# Sheet4.net
KiCad netlist of a schematic drawn in Altium Designer
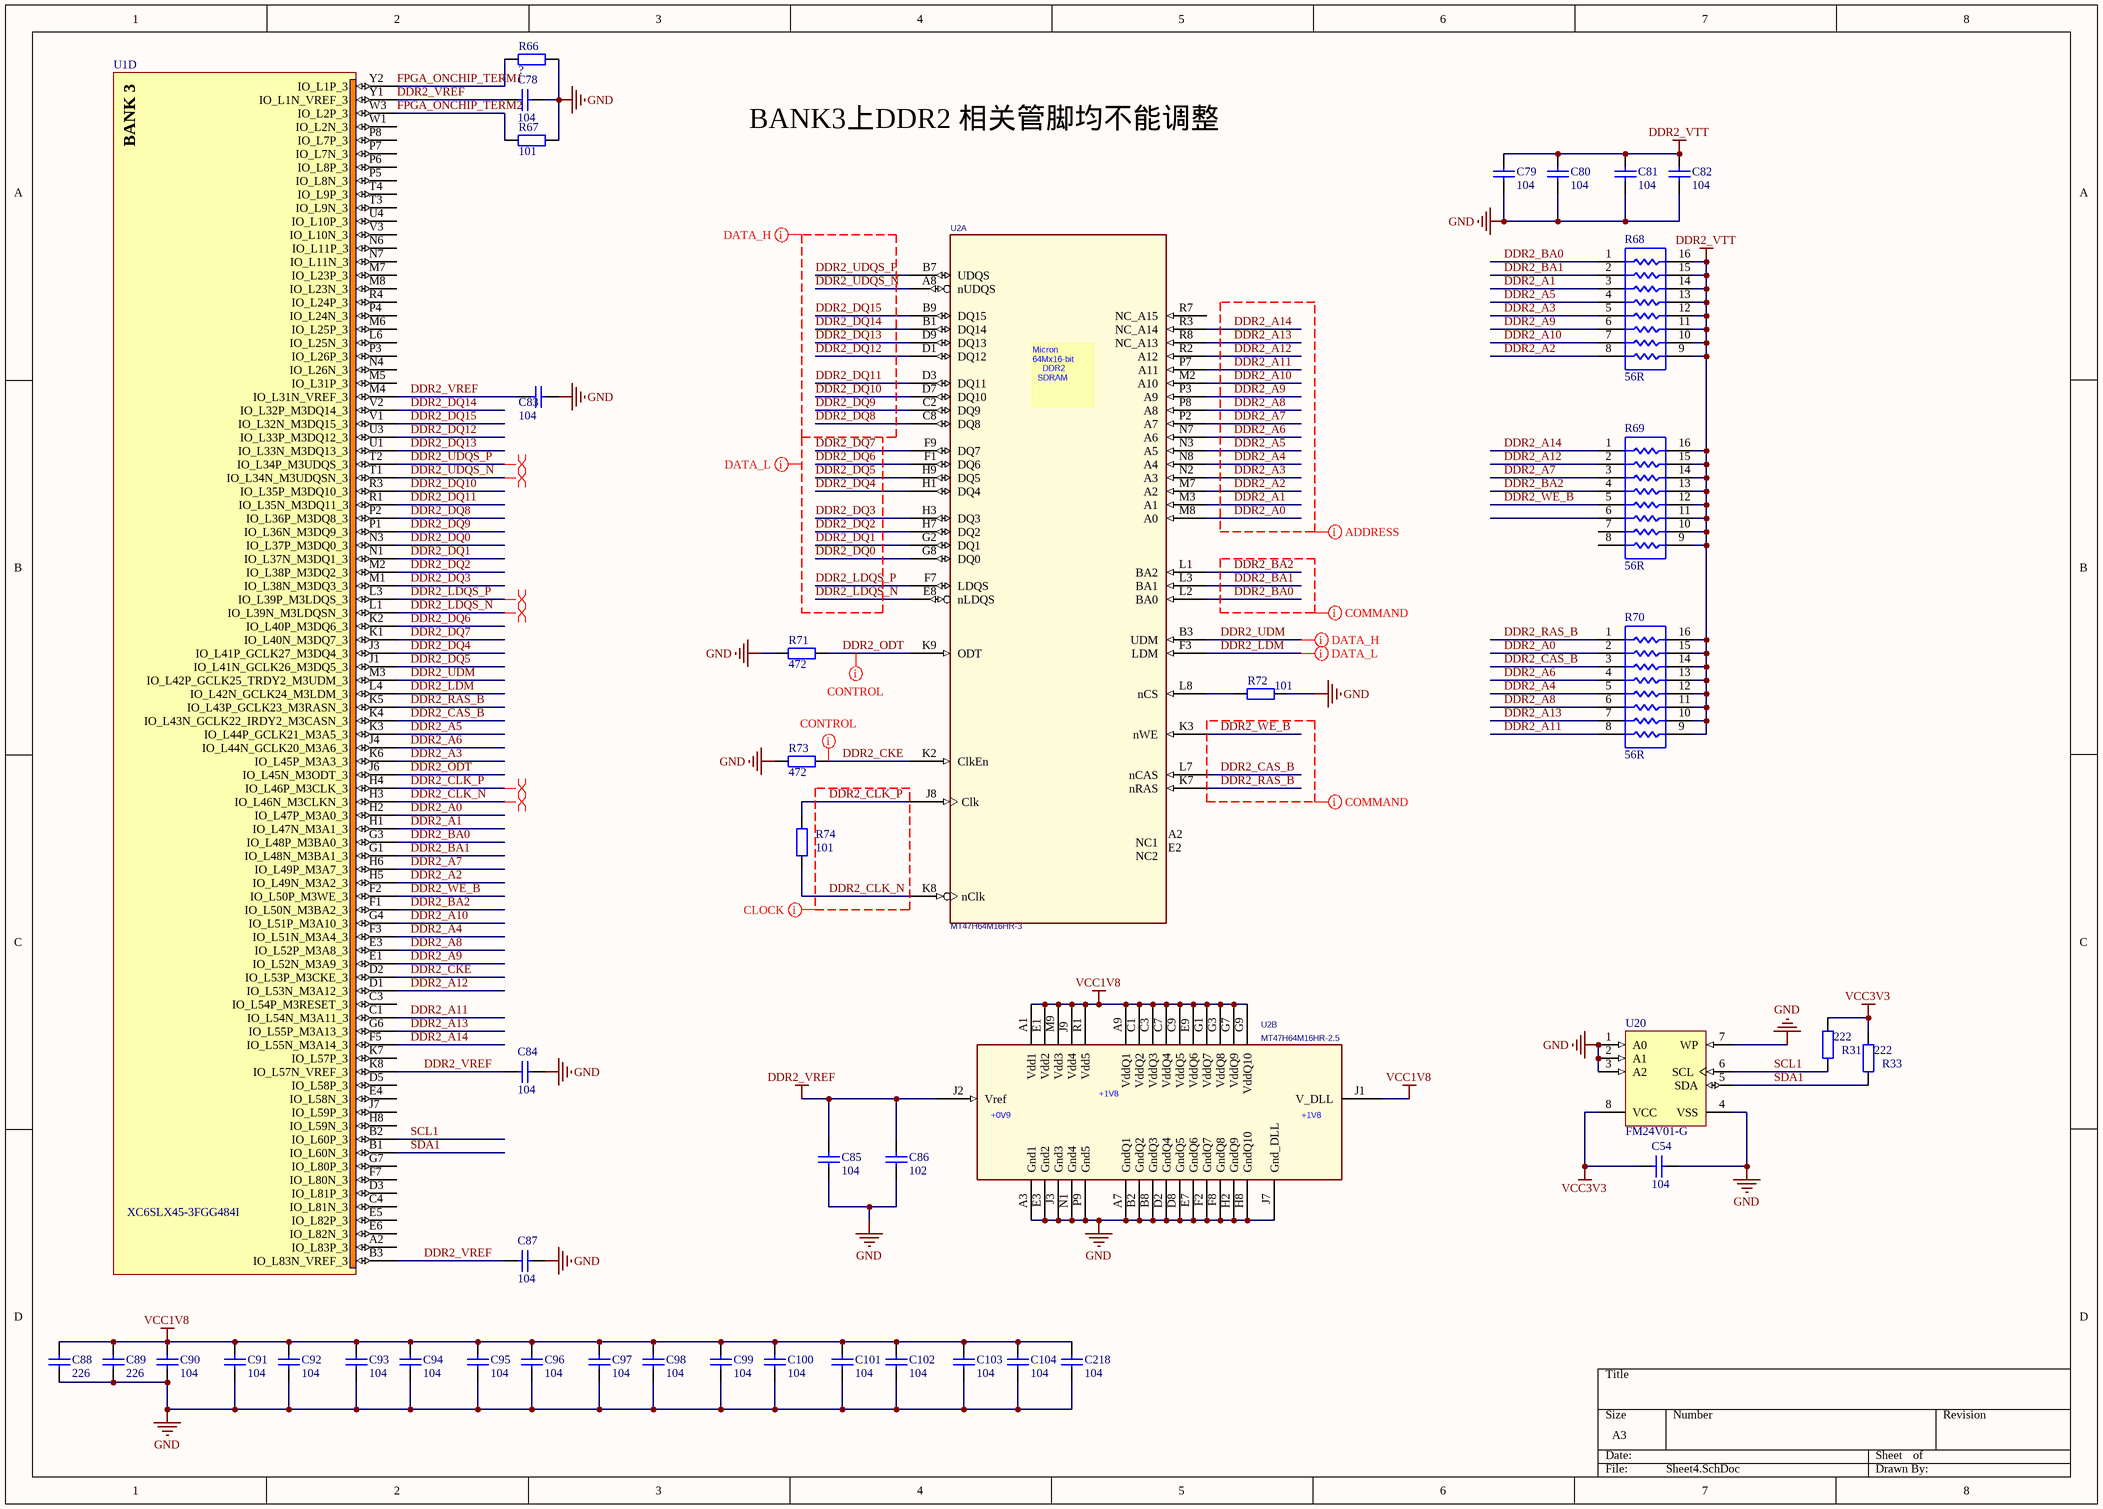
[diagram p0: Sheet4.SchDoc]

(export (version "E")
  (design (tool "Eeschema 10.0.6"))
  (components
    (comp (ref "C54")
      (value "104")
      (footprint "0402")
      (description "Capacitor")
      (fields (field (name "PUBLISHER") "Altium Limited"))
      (libsource (lib "Miscellaneous Devices") (part "Cap"))
    )
    (comp (ref "C78")
      (value "104")
      (footprint "0402")
      (description "Capacitor")
      (fields (field (name "PUBLISHER") "Altium Limited"))
      (libsource (lib "Miscellaneous Devices") (part "Cap"))
    )
    (comp (ref "C79")
      (value "104")
      (footprint "0402")
      (description "Capacitor")
      (fields (field (name "PUBLISHER") "Altium Limited"))
      (libsource (lib "Miscellaneous Devices") (part "Cap"))
    )
    (comp (ref "C80")
      (value "104")
      (footprint "0402")
      (description "Capacitor")
      (fields (field (name "PUBLISHER") "Altium Limited"))
      (libsource (lib "Miscellaneous Devices") (part "Cap"))
    )
    (comp (ref "C81")
      (value "104")
      (footprint "0402")
      (description "Capacitor")
      (fields (field (name "PUBLISHER") "Altium Limited"))
      (libsource (lib "Miscellaneous Devices") (part "Cap"))
    )
    (comp (ref "C82")
      (value "104")
      (footprint "0402")
      (description "Capacitor")
      (fields (field (name "PUBLISHER") "Altium Limited"))
      (libsource (lib "Miscellaneous Devices") (part "Cap"))
    )
    (comp (ref "C83")
      (value "104")
      (footprint "0402")
      (description "Capacitor")
      (fields (field (name "PUBLISHER") "Altium Limited"))
      (libsource (lib "Miscellaneous Devices") (part "Cap"))
    )
    (comp (ref "C84")
      (value "104")
      (footprint "0402")
      (description "Capacitor")
      (fields (field (name "PUBLISHER") "Altium Limited"))
      (libsource (lib "Miscellaneous Devices") (part "Cap"))
    )
    (comp (ref "C85")
      (value "104")
      (footprint "0402")
      (description "Capacitor")
      (fields (field (name "PUBLISHER") "Altium Limited"))
      (libsource (lib "Miscellaneous Devices") (part "Cap"))
    )
    (comp (ref "C86")
      (value "102")
      (footprint "0402")
      (description "Capacitor")
      (fields (field (name "PUBLISHER") "Altium Limited"))
      (libsource (lib "Miscellaneous Devices") (part "Cap"))
    )
    (comp (ref "C87")
      (value "104")
      (footprint "0402")
      (description "Capacitor")
      (fields (field (name "PUBLISHER") "Altium Limited"))
      (libsource (lib "Miscellaneous Devices") (part "Cap"))
    )
    (comp (ref "C88")
      (value "226")
      (footprint "0603")
      (description "Capacitor")
      (fields (field (name "PUBLISHER") "Altium Limited"))
      (libsource (lib "Miscellaneous Devices") (part "Cap"))
    )
    (comp (ref "C89")
      (value "226")
      (footprint "0603")
      (description "Capacitor")
      (fields (field (name "PUBLISHER") "Altium Limited"))
      (libsource (lib "Miscellaneous Devices") (part "Cap"))
    )
    (comp (ref "C90")
      (value "104")
      (footprint "0402")
      (description "Capacitor")
      (fields (field (name "PUBLISHER") "Altium Limited"))
      (libsource (lib "Miscellaneous Devices") (part "Cap"))
    )
    (comp (ref "C91")
      (value "104")
      (footprint "0402")
      (description "Capacitor")
      (fields (field (name "PUBLISHER") "Altium Limited"))
      (libsource (lib "Miscellaneous Devices") (part "Cap"))
    )
    (comp (ref "C92")
      (value "104")
      (footprint "0402")
      (description "Capacitor")
      (fields (field (name "PUBLISHER") "Altium Limited"))
      (libsource (lib "Miscellaneous Devices") (part "Cap"))
    )
    (comp (ref "C93")
      (value "104")
      (footprint "0402")
      (description "Capacitor")
      (fields (field (name "PUBLISHER") "Altium Limited"))
      (libsource (lib "Miscellaneous Devices") (part "Cap"))
    )
    (comp (ref "C94")
      (value "104")
      (footprint "0402")
      (description "Capacitor")
      (fields (field (name "PUBLISHER") "Altium Limited"))
      (libsource (lib "Miscellaneous Devices") (part "Cap"))
    )
    (comp (ref "C95")
      (value "104")
      (footprint "0402")
      (description "Capacitor")
      (fields (field (name "PUBLISHER") "Altium Limited"))
      (libsource (lib "Miscellaneous Devices") (part "Cap"))
    )
    (comp (ref "C96")
      (value "104")
      (footprint "0402")
      (description "Capacitor")
      (fields (field (name "PUBLISHER") "Altium Limited"))
      (libsource (lib "Miscellaneous Devices") (part "Cap"))
    )
    (comp (ref "C97")
      (value "104")
      (footprint "0402")
      (description "Capacitor")
      (fields (field (name "PUBLISHER") "Altium Limited"))
      (libsource (lib "Miscellaneous Devices") (part "Cap"))
    )
    (comp (ref "C98")
      (value "104")
      (footprint "0402")
      (description "Capacitor")
      (fields (field (name "PUBLISHER") "Altium Limited"))
      (libsource (lib "Miscellaneous Devices") (part "Cap"))
    )
    (comp (ref "C99")
      (value "104")
      (footprint "0402")
      (description "Capacitor")
      (fields (field (name "PUBLISHER") "Altium Limited"))
      (libsource (lib "Miscellaneous Devices") (part "Cap"))
    )
    (comp (ref "C100")
      (value "104")
      (footprint "0402")
      (description "Capacitor")
      (fields (field (name "PUBLISHER") "Altium Limited"))
      (libsource (lib "Miscellaneous Devices") (part "Cap"))
    )
    (comp (ref "C101")
      (value "104")
      (footprint "0402")
      (description "Capacitor")
      (fields (field (name "PUBLISHER") "Altium Limited"))
      (libsource (lib "Miscellaneous Devices") (part "Cap"))
    )
    (comp (ref "C102")
      (value "104")
      (footprint "0402")
      (description "Capacitor")
      (fields (field (name "PUBLISHER") "Altium Limited"))
      (libsource (lib "Miscellaneous Devices") (part "Cap"))
    )
    (comp (ref "C103")
      (value "104")
      (footprint "0402")
      (description "Capacitor")
      (fields (field (name "PUBLISHER") "Altium Limited"))
      (libsource (lib "Miscellaneous Devices") (part "Cap"))
    )
    (comp (ref "C104")
      (value "104")
      (footprint "0402")
      (description "Capacitor")
      (fields (field (name "PUBLISHER") "Altium Limited"))
      (libsource (lib "Miscellaneous Devices") (part "Cap"))
    )
    (comp (ref "C218")
      (value "104")
      (footprint "0402")
      (description "Capacitor")
      (fields (field (name "PUBLISHER") "Altium Limited"))
      (libsource (lib "Miscellaneous Devices") (part "Cap"))
    )
    (comp (ref "R31")
      (value "222")
      (footprint "0603")
      (description "Resistor")
      (fields (field (name "PUBLISHER") "Altium Limited"))
      (libsource (lib "Miscellaneous Devices") (part "Res2"))
    )
    (comp (ref "R33")
      (value "222")
      (footprint "0603")
      (description "Resistor")
      (fields (field (name "PUBLISHER") "Altium Limited"))
      (libsource (lib "Miscellaneous Devices") (part "Res2"))
    )
    (comp (ref "R66")
      (value "?")
      (footprint "0603")
      (description "Resistor")
      (fields (field (name "PUBLISHER") "Altium Limited"))
      (libsource (lib "") (part "Res2_1"))
    )
    (comp (ref "R67")
      (value "101")
      (footprint "0603")
      (description "Resistor")
      (fields (field (name "PUBLISHER") "Altium Limited"))
      (libsource (lib "") (part "Res2_1"))
    )
    (comp (ref "R68")
      (value "56R")
      (footprint "RESROW_8")
      (description "Isolated Resistor Network")
      (fields (field (name "PUBLISHER") "Altium Limited"))
      (libsource (lib "Miscellaneous Devices") (part "Res Pack3"))
    )
    (comp (ref "R69")
      (value "56R")
      (footprint "RESROW_8")
      (description "Isolated Resistor Network")
      (fields (field (name "PUBLISHER") "Altium Limited"))
      (libsource (lib "Miscellaneous Devices") (part "Res Pack3"))
    )
    (comp (ref "R70")
      (value "56R")
      (footprint "RESROW_8")
      (description "Isolated Resistor Network")
      (fields (field (name "PUBLISHER") "Altium Limited"))
      (libsource (lib "Miscellaneous Devices") (part "Res Pack3"))
    )
    (comp (ref "R71")
      (value "472")
      (footprint "0402")
      (description "Resistor")
      (fields (field (name "PUBLISHER") "Altium Limited"))
      (libsource (lib "") (part "Res2_1"))
    )
    (comp (ref "R72")
      (value "101")
      (footprint "0402")
      (description "Resistor")
      (fields (field (name "PUBLISHER") "Altium Limited"))
      (libsource (lib "") (part "Res2_1"))
    )
    (comp (ref "R73")
      (value "472")
      (footprint "0402")
      (description "Resistor")
      (fields (field (name "PUBLISHER") "Altium Limited"))
      (libsource (lib "") (part "Res2_1"))
    )
    (comp (ref "R74")
      (value "101")
      (footprint "0402")
      (description "Resistor")
      (fields (field (name "PUBLISHER") "Altium Limited"))
      (libsource (lib "") (part "Res2_2"))
    )
    (comp (ref "U1")
      (value "XC6SLX45-3FGG484I")
      (footprint "FGG484")
      (fields (field (name "PUBLISHER") "Altium Limited"))
      (libsource (lib "Xilinx Spartan-6") (part "XC6SLX45-3FGG484I"))
    )
    (comp (ref "U2")
      (value "MT47H64M16HR-3")
      (footprint "FBGA_84 - OK")
      (description "64Mx16-bit DDR2 SDRAM")
      (fields (field (name "MANUFACTURER") "Micron") (field (name "FULL PART NO") "MT47H64M16HR-25"))
      (libsource (lib "Mpd_Fpga") (part "DDR2 64Mx16 MT47H64M16HR-25"))
    )
    (comp (ref "U20")
      (value "FM24V01-G")
      (footprint "SMD8XX")
      (description "2Kbit, 400kHz, 2.5V, I2C Serial EEPROM, 8-Pin SOIC 150mil, Industrial Temperature")
      (fields (field (name "PUBLISHER") "Altium Limited"))
      (libsource (lib "Microchip Memory I2C Serial EEPROM") (part "24LC02B-I/SN"))
    )
  )
  (nets
    (net (code "1") (name "/DDR2_A0") (class "Default")
      (node (ref "R70") (pin "2") (pinfunction "2_2") (pintype "passive"))
      (node (ref "U1") (pin "H2") (pinfunction "IO_L47P_M3A0_3_H2") (pintype "bidirectional"))
      (node (ref "U2") (pin "M8") (pinfunction "A0_M8") (pintype "input"))
    )
    (net (code "2") (name "/DDR2_A1") (class "Default")
      (node (ref "R68") (pin "3") (pinfunction "3_3") (pintype "passive"))
      (node (ref "U1") (pin "H1") (pinfunction "IO_L47N_M3A1_3_H1") (pintype "bidirectional"))
      (node (ref "U2") (pin "M3") (pinfunction "A1_M3") (pintype "input"))
    )
    (net (code "3") (name "/DDR2_A2") (class "Default")
      (node (ref "R68") (pin "8") (pinfunction "8_8") (pintype "passive"))
      (node (ref "U1") (pin "H5") (pinfunction "IO_L49N_M3A2_3_H5") (pintype "bidirectional"))
      (node (ref "U2") (pin "M7") (pinfunction "A2_M7") (pintype "input"))
    )
    (net (code "4") (name "/DDR2_A3") (class "Default")
      (node (ref "R68") (pin "5") (pinfunction "5_5") (pintype "passive"))
      (node (ref "U1") (pin "K6") (pinfunction "IO_L45P_M3A3_3_K6") (pintype "bidirectional"))
      (node (ref "U2") (pin "N2") (pinfunction "A3_N2") (pintype "input"))
    )
    (net (code "5") (name "/DDR2_A4") (class "Default")
      (node (ref "R70") (pin "5") (pinfunction "5_5") (pintype "passive"))
      (node (ref "U1") (pin "F3") (pinfunction "IO_L51N_M3A4_3_F3") (pintype "bidirectional"))
      (node (ref "U2") (pin "N8") (pinfunction "A4_N8") (pintype "input"))
    )
    (net (code "6") (name "/DDR2_A5") (class "Default")
      (node (ref "R68") (pin "4") (pinfunction "4_4") (pintype "passive"))
      (node (ref "U1") (pin "K3") (pinfunction "IO_L44P_GCLK21_M3A5_3_K3") (pintype "bidirectional"))
      (node (ref "U2") (pin "N3") (pinfunction "A5_N3") (pintype "input"))
    )
    (net (code "7") (name "/DDR2_A6") (class "Default")
      (node (ref "R70") (pin "4") (pinfunction "4_4") (pintype "passive"))
      (node (ref "U1") (pin "J4") (pinfunction "IO_L44N_GCLK20_M3A6_3_J4") (pintype "bidirectional"))
      (node (ref "U2") (pin "N7") (pinfunction "A6_N7") (pintype "input"))
    )
    (net (code "8") (name "/DDR2_A7") (class "Default")
      (node (ref "R69") (pin "3") (pinfunction "3_3") (pintype "passive"))
      (node (ref "U1") (pin "H6") (pinfunction "IO_L49P_M3A7_3_H6") (pintype "bidirectional"))
      (node (ref "U2") (pin "P2") (pinfunction "A7_P2") (pintype "input"))
    )
    (net (code "9") (name "/DDR2_A8") (class "Default")
      (node (ref "R70") (pin "6") (pinfunction "6_6") (pintype "passive"))
      (node (ref "U1") (pin "E3") (pinfunction "IO_L52P_M3A8_3_E3") (pintype "bidirectional"))
      (node (ref "U2") (pin "P8") (pinfunction "A8_P8") (pintype "input"))
    )
    (net (code "10") (name "/DDR2_A9") (class "Default")
      (node (ref "R68") (pin "6") (pinfunction "6_6") (pintype "passive"))
      (node (ref "U1") (pin "E1") (pinfunction "IO_L52N_M3A9_3_E1") (pintype "bidirectional"))
      (node (ref "U2") (pin "P3") (pinfunction "A9_P3") (pintype "input"))
    )
    (net (code "11") (name "/DDR2_A10") (class "Default")
      (node (ref "R68") (pin "7") (pinfunction "7_7") (pintype "passive"))
      (node (ref "U1") (pin "G4") (pinfunction "IO_L51P_M3A10_3_G4") (pintype "bidirectional"))
      (node (ref "U2") (pin "M2") (pinfunction "A10_M2") (pintype "input"))
    )
    (net (code "12") (name "/DDR2_A11") (class "Default")
      (node (ref "R70") (pin "8") (pinfunction "8_8") (pintype "passive"))
      (node (ref "U1") (pin "C1") (pinfunction "IO_L54N_M3A11_3_C1") (pintype "bidirectional"))
      (node (ref "U2") (pin "P7") (pinfunction "A11_P7") (pintype "input"))
    )
    (net (code "13") (name "/DDR2_A12") (class "Default")
      (node (ref "R69") (pin "2") (pinfunction "2_2") (pintype "passive"))
      (node (ref "U1") (pin "D1") (pinfunction "IO_L53N_M3A12_3_D1") (pintype "bidirectional"))
      (node (ref "U2") (pin "R2") (pinfunction "A12_R2") (pintype "input"))
    )
    (net (code "14") (name "/DDR2_A13") (class "Default")
      (node (ref "R70") (pin "7") (pinfunction "7_7") (pintype "passive"))
      (node (ref "U1") (pin "G6") (pinfunction "IO_L55P_M3A13_3_G6") (pintype "bidirectional"))
      (node (ref "U2") (pin "R8") (pinfunction "NC_A13_R8") (pintype "input"))
    )
    (net (code "15") (name "/DDR2_A14") (class "Default")
      (node (ref "R69") (pin "1") (pinfunction "1_1") (pintype "passive"))
      (node (ref "U1") (pin "F5") (pinfunction "IO_L55N_M3A14_3_F5") (pintype "bidirectional"))
      (node (ref "U2") (pin "R3") (pinfunction "NC_A14_R3") (pintype "input"))
    )
    (net (code "16") (name "/DDR2_BA0") (class "Default")
      (node (ref "R68") (pin "1") (pinfunction "1_1") (pintype "passive"))
      (node (ref "U1") (pin "G3") (pinfunction "IO_L48P_M3BA0_3_G3") (pintype "bidirectional"))
      (node (ref "U2") (pin "L2") (pinfunction "BA0_L2") (pintype "input"))
    )
    (net (code "17") (name "/DDR2_BA1") (class "Default")
      (node (ref "R68") (pin "2") (pinfunction "2_2") (pintype "passive"))
      (node (ref "U1") (pin "G1") (pinfunction "IO_L48N_M3BA1_3_G1") (pintype "bidirectional"))
      (node (ref "U2") (pin "L3") (pinfunction "BA1_L3") (pintype "input"))
    )
    (net (code "18") (name "/DDR2_BA2") (class "Default")
      (node (ref "R69") (pin "4") (pinfunction "4_4") (pintype "passive"))
      (node (ref "U1") (pin "F1") (pinfunction "IO_L50N_M3BA2_3_F1") (pintype "bidirectional"))
      (node (ref "U2") (pin "L1") (pinfunction "BA2_L1") (pintype "input"))
    )
    (net (code "19") (name "/DDR2_CAS_B") (class "Default")
      (node (ref "R70") (pin "3") (pinfunction "3_3") (pintype "passive"))
      (node (ref "U1") (pin "K4") (pinfunction "IO_L43N_GCLK22_IRDY2_M3CASN_3_K4") (pintype "bidirectional"))
      (node (ref "U2") (pin "L7") (pinfunction "nCAS_L7") (pintype "input"))
    )
    (net (code "20") (name "/DDR2_CKE") (class "Default")
      (node (ref "R73") (pin "2") (pinfunction "2_2") (pintype "passive"))
      (node (ref "U1") (pin "D2") (pinfunction "IO_L53P_M3CKE_3_D2") (pintype "bidirectional"))
      (node (ref "U2") (pin "K2") (pinfunction "ClkEn_K2") (pintype "input"))
    )
    (net (code "21") (name "/DDR2_CLK_N") (class "Default")
      (node (ref "R74") (pin "1") (pinfunction "1_1") (pintype "passive"))
      (node (ref "U1") (pin "H3") (pinfunction "IO_L46N_M3CLKN_3_H3") (pintype "bidirectional"))
      (node (ref "U2") (pin "K8") (pinfunction "nClk_K8") (pintype "input"))
    )
    (net (code "22") (name "/DDR2_CLK_P") (class "Default")
      (node (ref "R74") (pin "2") (pinfunction "2_2") (pintype "passive"))
      (node (ref "U1") (pin "H4") (pinfunction "IO_L46P_M3CLK_3_H4") (pintype "bidirectional"))
      (node (ref "U2") (pin "J8") (pinfunction "Clk_J8") (pintype "input"))
    )
    (net (code "23") (name "/DDR2_DQ0") (class "Default")
      (node (ref "U1") (pin "N3") (pinfunction "IO_L37P_M3DQ0_3_N3") (pintype "bidirectional"))
      (node (ref "U2") (pin "G8") (pinfunction "DQ0_G8") (pintype "bidirectional"))
    )
    (net (code "24") (name "/DDR2_DQ1") (class "Default")
      (node (ref "U1") (pin "N1") (pinfunction "IO_L37N_M3DQ1_3_N1") (pintype "bidirectional"))
      (node (ref "U2") (pin "G2") (pinfunction "DQ1_G2") (pintype "bidirectional"))
    )
    (net (code "25") (name "/DDR2_DQ2") (class "Default")
      (node (ref "U1") (pin "M2") (pinfunction "IO_L38P_M3DQ2_3_M2") (pintype "bidirectional"))
      (node (ref "U2") (pin "H7") (pinfunction "DQ2_H7") (pintype "bidirectional"))
    )
    (net (code "26") (name "/DDR2_DQ3") (class "Default")
      (node (ref "U1") (pin "M1") (pinfunction "IO_L38N_M3DQ3_3_M1") (pintype "bidirectional"))
      (node (ref "U2") (pin "H3") (pinfunction "DQ3_H3") (pintype "bidirectional"))
    )
    (net (code "27") (name "/DDR2_DQ4") (class "Default")
      (node (ref "U1") (pin "J3") (pinfunction "IO_L41P_GCLK27_M3DQ4_3_J3") (pintype "bidirectional"))
      (node (ref "U2") (pin "H1") (pinfunction "DQ4_H1") (pintype "bidirectional"))
    )
    (net (code "28") (name "/DDR2_DQ5") (class "Default")
      (node (ref "U1") (pin "J1") (pinfunction "IO_L41N_GCLK26_M3DQ5_3_J1") (pintype "bidirectional"))
      (node (ref "U2") (pin "H9") (pinfunction "DQ5_H9") (pintype "bidirectional"))
    )
    (net (code "29") (name "/DDR2_DQ6") (class "Default")
      (node (ref "U1") (pin "K2") (pinfunction "IO_L40P_M3DQ6_3_K2") (pintype "bidirectional"))
      (node (ref "U2") (pin "F1") (pinfunction "DQ6_F1") (pintype "bidirectional"))
    )
    (net (code "30") (name "/DDR2_DQ7") (class "Default")
      (node (ref "U1") (pin "K1") (pinfunction "IO_L40N_M3DQ7_3_K1") (pintype "bidirectional"))
      (node (ref "U2") (pin "F9") (pinfunction "DQ7_F9") (pintype "bidirectional"))
    )
    (net (code "31") (name "/DDR2_DQ8") (class "Default")
      (node (ref "U1") (pin "P2") (pinfunction "IO_L36P_M3DQ8_3_P2") (pintype "bidirectional"))
      (node (ref "U2") (pin "C8") (pinfunction "DQ8_C8") (pintype "bidirectional"))
    )
    (net (code "32") (name "/DDR2_DQ9") (class "Default")
      (node (ref "U1") (pin "P1") (pinfunction "IO_L36N_M3DQ9_3_P1") (pintype "bidirectional"))
      (node (ref "U2") (pin "C2") (pinfunction "DQ9_C2") (pintype "bidirectional"))
    )
    (net (code "33") (name "/DDR2_DQ10") (class "Default")
      (node (ref "U1") (pin "R3") (pinfunction "IO_L35P_M3DQ10_3_R3") (pintype "bidirectional"))
      (node (ref "U2") (pin "D7") (pinfunction "DQ10_D7") (pintype "bidirectional"))
    )
    (net (code "34") (name "/DDR2_DQ11") (class "Default")
      (node (ref "U1") (pin "R1") (pinfunction "IO_L35N_M3DQ11_3_R1") (pintype "bidirectional"))
      (node (ref "U2") (pin "D3") (pinfunction "DQ11_D3") (pintype "bidirectional"))
    )
    (net (code "35") (name "/DDR2_DQ12") (class "Default")
      (node (ref "U1") (pin "U3") (pinfunction "IO_L33P_M3DQ12_3_U3") (pintype "bidirectional"))
      (node (ref "U2") (pin "D1") (pinfunction "DQ12_D1") (pintype "bidirectional"))
    )
    (net (code "36") (name "/DDR2_DQ13") (class "Default")
      (node (ref "U1") (pin "U1") (pinfunction "IO_L33N_M3DQ13_3_U1") (pintype "bidirectional"))
      (node (ref "U2") (pin "D9") (pinfunction "DQ13_D9") (pintype "bidirectional"))
    )
    (net (code "37") (name "/DDR2_DQ14") (class "Default")
      (node (ref "U1") (pin "V2") (pinfunction "IO_L32P_M3DQ14_3_V2") (pintype "bidirectional"))
      (node (ref "U2") (pin "B1") (pinfunction "DQ14_B1") (pintype "bidirectional"))
    )
    (net (code "38") (name "/DDR2_DQ15") (class "Default")
      (node (ref "U1") (pin "V1") (pinfunction "IO_L32N_M3DQ15_3_V1") (pintype "bidirectional"))
      (node (ref "U2") (pin "B9") (pinfunction "DQ15_B9") (pintype "bidirectional"))
    )
    (net (code "39") (name "/DDR2_LDM") (class "Default")
      (node (ref "U1") (pin "L4") (pinfunction "IO_L42N_GCLK24_M3LDM_3_L4") (pintype "bidirectional"))
      (node (ref "U2") (pin "F3") (pinfunction "LDM_F3") (pintype "input"))
    )
    (net (code "40") (name "/DDR2_LDQS_N") (class "Default")
      (node (ref "U1") (pin "L1") (pinfunction "IO_L39N_M3LDQSN_3_L1") (pintype "bidirectional"))
      (node (ref "U2") (pin "E8") (pinfunction "nLDQS_E8") (pintype "bidirectional"))
    )
    (net (code "41") (name "/DDR2_LDQS_P") (class "Default")
      (node (ref "U1") (pin "L3") (pinfunction "IO_L39P_M3LDQS_3_L3") (pintype "bidirectional"))
      (node (ref "U2") (pin "F7") (pinfunction "LDQS_F7") (pintype "bidirectional"))
    )
    (net (code "42") (name "/DDR2_ODT") (class "Default")
      (node (ref "R71") (pin "2") (pinfunction "2_2") (pintype "passive"))
      (node (ref "U1") (pin "J6") (pinfunction "IO_L45N_M3ODT_3_J6") (pintype "bidirectional"))
      (node (ref "U2") (pin "K9") (pinfunction "ODT_K9") (pintype "input"))
    )
    (net (code "43") (name "/DDR2_RAS_B") (class "Default")
      (node (ref "R70") (pin "1") (pinfunction "1_1") (pintype "passive"))
      (node (ref "U1") (pin "K5") (pinfunction "IO_L43P_GCLK23_M3RASN_3_K5") (pintype "bidirectional"))
      (node (ref "U2") (pin "K7") (pinfunction "nRAS_K7") (pintype "input"))
    )
    (net (code "44") (name "/DDR2_UDM") (class "Default")
      (node (ref "U1") (pin "M3") (pinfunction "IO_L42P_GCLK25_TRDY2_M3UDM_3_M3") (pintype "bidirectional"))
      (node (ref "U2") (pin "B3") (pinfunction "UDM_B3") (pintype "input"))
    )
    (net (code "45") (name "/DDR2_UDQS_N") (class "Default")
      (node (ref "U1") (pin "T1") (pinfunction "IO_L34N_M3UDQSN_3_T1") (pintype "bidirectional"))
      (node (ref "U2") (pin "A8") (pinfunction "nUDQS_A8") (pintype "bidirectional"))
    )
    (net (code "46") (name "/DDR2_UDQS_P") (class "Default")
      (node (ref "U1") (pin "T2") (pinfunction "IO_L34P_M3UDQS_3_T2") (pintype "bidirectional"))
      (node (ref "U2") (pin "B7") (pinfunction "UDQS_B7") (pintype "bidirectional"))
    )
    (net (code "47") (name "/DDR2_WE_B") (class "Default")
      (node (ref "R69") (pin "5") (pinfunction "5_5") (pintype "passive"))
      (node (ref "U1") (pin "F2") (pinfunction "IO_L50P_M3WE_3_F2") (pintype "bidirectional"))
      (node (ref "U2") (pin "K3") (pinfunction "nWE_K3") (pintype "input"))
    )
    (net (code "48") (name "/FPGA_ONCHIP_TERM1") (class "Default")
      (node (ref "R66") (pin "1") (pinfunction "1_1") (pintype "passive"))
      (node (ref "U1") (pin "Y2") (pinfunction "IO_L1P_3_Y2") (pintype "bidirectional"))
    )
    (net (code "49") (name "/FPGA_ONCHIP_TERM2") (class "Default")
      (node (ref "R67") (pin "1") (pinfunction "1_1") (pintype "passive"))
      (node (ref "U1") (pin "W3") (pinfunction "IO_L2P_3_W3") (pintype "bidirectional"))
    )
    (net (code "50") (name "/SCL1") (class "Default")
      (node (ref "R31") (pin "2") (pinfunction "2_2") (pintype "passive"))
      (node (ref "U1") (pin "B2") (pinfunction "IO_L60P_3_B2") (pintype "bidirectional"))
      (node (ref "U20") (pin "6") (pinfunction "SCL_6") (pintype "input"))
    )
    (net (code "51") (name "/SDA1") (class "Default")
      (node (ref "R33") (pin "2") (pinfunction "2_2") (pintype "passive"))
      (node (ref "U1") (pin "B1") (pinfunction "IO_L60N_3_B1") (pintype "bidirectional"))
      (node (ref "U20") (pin "5") (pinfunction "SDA_5") (pintype "bidirectional"))
    )
    (net (code "52") (name "DDR2_VREF") (class "Default")
      (node (ref "C78") (pin "2") (pinfunction "2_2") (pintype "passive"))
      (node (ref "C83") (pin "2") (pinfunction "2_2") (pintype "passive"))
      (node (ref "C84") (pin "2") (pinfunction "2_2") (pintype "passive"))
      (node (ref "C85") (pin "2") (pinfunction "2_2") (pintype "passive"))
      (node (ref "C86") (pin "2") (pinfunction "2_2") (pintype "passive"))
      (node (ref "C87") (pin "2") (pinfunction "2_2") (pintype "passive"))
      (node (ref "U1") (pin "B3") (pinfunction "IO_L83N_VREF_3_B3") (pintype "bidirectional"))
      (node (ref "U1") (pin "K8") (pinfunction "IO_L57N_VREF_3_K8") (pintype "bidirectional"))
      (node (ref "U1") (pin "M4") (pinfunction "IO_L31N_VREF_3_M4") (pintype "bidirectional"))
      (node (ref "U1") (pin "Y1") (pinfunction "IO_L1N_VREF_3_Y1") (pintype "bidirectional"))
      (node (ref "U2") (pin "J2") (pinfunction "Vref_J2") (pintype "input"))
    )
    (net (code "53") (name "DDR2_VTT") (class "Default")
      (node (ref "C79") (pin "2") (pinfunction "2_2") (pintype "passive"))
      (node (ref "C80") (pin "2") (pinfunction "2_2") (pintype "passive"))
      (node (ref "C81") (pin "2") (pinfunction "2_2") (pintype "passive"))
      (node (ref "C82") (pin "2") (pinfunction "2_2") (pintype "passive"))
      (node (ref "R68") (pin "10") (pinfunction "10_10") (pintype "passive"))
      (node (ref "R68") (pin "11") (pinfunction "11_11") (pintype "passive"))
      (node (ref "R68") (pin "12") (pinfunction "12_12") (pintype "passive"))
      (node (ref "R68") (pin "13") (pinfunction "13_13") (pintype "passive"))
      (node (ref "R68") (pin "14") (pinfunction "14_14") (pintype "passive"))
      (node (ref "R68") (pin "15") (pinfunction "15_15") (pintype "passive"))
      (node (ref "R68") (pin "16") (pinfunction "16_16") (pintype "passive"))
      (node (ref "R68") (pin "9") (pinfunction "9_9") (pintype "passive"))
      (node (ref "R69") (pin "10") (pinfunction "10_10") (pintype "passive"))
      (node (ref "R69") (pin "11") (pinfunction "11_11") (pintype "passive"))
      (node (ref "R69") (pin "12") (pinfunction "12_12") (pintype "passive"))
      (node (ref "R69") (pin "13") (pinfunction "13_13") (pintype "passive"))
      (node (ref "R69") (pin "14") (pinfunction "14_14") (pintype "passive"))
      (node (ref "R69") (pin "15") (pinfunction "15_15") (pintype "passive"))
      (node (ref "R69") (pin "16") (pinfunction "16_16") (pintype "passive"))
      (node (ref "R69") (pin "9") (pinfunction "9_9") (pintype "passive"))
      (node (ref "R70") (pin "10") (pinfunction "10_10") (pintype "passive"))
      (node (ref "R70") (pin "11") (pinfunction "11_11") (pintype "passive"))
      (node (ref "R70") (pin "12") (pinfunction "12_12") (pintype "passive"))
      (node (ref "R70") (pin "13") (pinfunction "13_13") (pintype "passive"))
      (node (ref "R70") (pin "14") (pinfunction "14_14") (pintype "passive"))
      (node (ref "R70") (pin "15") (pinfunction "15_15") (pintype "passive"))
      (node (ref "R70") (pin "16") (pinfunction "16_16") (pintype "passive"))
      (node (ref "R70") (pin "9") (pinfunction "9_9") (pintype "passive"))
    )
    (net (code "54") (name "GND") (class "Default")
      (node (ref "C100") (pin "1") (pinfunction "1_1") (pintype "passive"))
      (node (ref "C101") (pin "1") (pinfunction "1_1") (pintype "passive"))
      (node (ref "C102") (pin "1") (pinfunction "1_1") (pintype "passive"))
      (node (ref "C103") (pin "1") (pinfunction "1_1") (pintype "passive"))
      (node (ref "C104") (pin "1") (pinfunction "1_1") (pintype "passive"))
      (node (ref "C218") (pin "1") (pinfunction "1_1") (pintype "passive"))
      (node (ref "C54") (pin "1") (pinfunction "1_1") (pintype "passive"))
      (node (ref "C78") (pin "1") (pinfunction "1_1") (pintype "passive"))
      (node (ref "C79") (pin "1") (pinfunction "1_1") (pintype "passive"))
      (node (ref "C80") (pin "1") (pinfunction "1_1") (pintype "passive"))
      (node (ref "C81") (pin "1") (pinfunction "1_1") (pintype "passive"))
      (node (ref "C82") (pin "1") (pinfunction "1_1") (pintype "passive"))
      (node (ref "C83") (pin "1") (pinfunction "1_1") (pintype "passive"))
      (node (ref "C84") (pin "1") (pinfunction "1_1") (pintype "passive"))
      (node (ref "C85") (pin "1") (pinfunction "1_1") (pintype "passive"))
      (node (ref "C86") (pin "1") (pinfunction "1_1") (pintype "passive"))
      (node (ref "C87") (pin "1") (pinfunction "1_1") (pintype "passive"))
      (node (ref "C88") (pin "1") (pinfunction "1_1") (pintype "passive"))
      (node (ref "C89") (pin "1") (pinfunction "1_1") (pintype "passive"))
      (node (ref "C90") (pin "1") (pinfunction "1_1") (pintype "passive"))
      (node (ref "C91") (pin "1") (pinfunction "1_1") (pintype "passive"))
      (node (ref "C92") (pin "1") (pinfunction "1_1") (pintype "passive"))
      (node (ref "C93") (pin "1") (pinfunction "1_1") (pintype "passive"))
      (node (ref "C94") (pin "1") (pinfunction "1_1") (pintype "passive"))
      (node (ref "C95") (pin "1") (pinfunction "1_1") (pintype "passive"))
      (node (ref "C96") (pin "1") (pinfunction "1_1") (pintype "passive"))
      (node (ref "C97") (pin "1") (pinfunction "1_1") (pintype "passive"))
      (node (ref "C98") (pin "1") (pinfunction "1_1") (pintype "passive"))
      (node (ref "C99") (pin "1") (pinfunction "1_1") (pintype "passive"))
      (node (ref "R66") (pin "2") (pinfunction "2_2") (pintype "passive"))
      (node (ref "R67") (pin "2") (pinfunction "2_2") (pintype "passive"))
      (node (ref "R71") (pin "1") (pinfunction "1_1") (pintype "passive"))
      (node (ref "R72") (pin "2") (pinfunction "2_2") (pintype "passive"))
      (node (ref "R73") (pin "1") (pinfunction "1_1") (pintype "passive"))
      (node (ref "U2") (pin "A3") (pinfunction "Gnd1_A3") (pintype "power_in"))
      (node (ref "U2") (pin "A7") (pinfunction "GndQ1_A7") (pintype "power_in"))
      (node (ref "U2") (pin "B2") (pinfunction "GndQ2_B2") (pintype "power_in"))
      (node (ref "U2") (pin "B8") (pinfunction "GndQ3_B8") (pintype "power_in"))
      (node (ref "U2") (pin "D2") (pinfunction "GndQ4_D2") (pintype "power_in"))
      (node (ref "U2") (pin "D8") (pinfunction "GndQ5_D8") (pintype "power_in"))
      (node (ref "U2") (pin "E3") (pinfunction "Gnd2_E3") (pintype "power_in"))
      (node (ref "U2") (pin "E7") (pinfunction "GndQ6_E7") (pintype "power_in"))
      (node (ref "U2") (pin "F2") (pinfunction "GndQ7_F2") (pintype "power_in"))
      (node (ref "U2") (pin "F8") (pinfunction "GndQ8_F8") (pintype "power_in"))
      (node (ref "U2") (pin "H2") (pinfunction "GndQ9_H2") (pintype "power_in"))
      (node (ref "U2") (pin "H8") (pinfunction "GndQ10_H8") (pintype "power_in"))
      (node (ref "U2") (pin "J3") (pinfunction "Gnd3_J3") (pintype "power_in"))
      (node (ref "U2") (pin "J7") (pinfunction "Gnd_DLL_J7") (pintype "power_in"))
      (node (ref "U2") (pin "N1") (pinfunction "Gnd4_N1") (pintype "power_in"))
      (node (ref "U2") (pin "P9") (pinfunction "Gnd5_P9") (pintype "power_in"))
      (node (ref "U20") (pin "1") (pinfunction "A0_1") (pintype "input"))
      (node (ref "U20") (pin "2") (pinfunction "A1_2") (pintype "input"))
      (node (ref "U20") (pin "3") (pinfunction "A2_3") (pintype "input"))
      (node (ref "U20") (pin "4") (pinfunction "VSS_4") (pintype "power_in"))
      (node (ref "U20") (pin "7") (pinfunction "WP_7") (pintype "input"))
    )
    (net (code "55") (name "Net-(U2A-nCS)") (class "Default")
      (node (ref "R72") (pin "1") (pinfunction "1_1") (pintype "passive"))
      (node (ref "U2") (pin "L8") (pinfunction "nCS_L8") (pintype "input"))
    )
    (net (code "56") (name "VCC1V8") (class "Default")
      (node (ref "C100") (pin "2") (pinfunction "2_2") (pintype "passive"))
      (node (ref "C101") (pin "2") (pinfunction "2_2") (pintype "passive"))
      (node (ref "C102") (pin "2") (pinfunction "2_2") (pintype "passive"))
      (node (ref "C103") (pin "2") (pinfunction "2_2") (pintype "passive"))
      (node (ref "C104") (pin "2") (pinfunction "2_2") (pintype "passive"))
      (node (ref "C218") (pin "2") (pinfunction "2_2") (pintype "passive"))
      (node (ref "C88") (pin "2") (pinfunction "2_2") (pintype "passive"))
      (node (ref "C89") (pin "2") (pinfunction "2_2") (pintype "passive"))
      (node (ref "C90") (pin "2") (pinfunction "2_2") (pintype "passive"))
      (node (ref "C91") (pin "2") (pinfunction "2_2") (pintype "passive"))
      (node (ref "C92") (pin "2") (pinfunction "2_2") (pintype "passive"))
      (node (ref "C93") (pin "2") (pinfunction "2_2") (pintype "passive"))
      (node (ref "C94") (pin "2") (pinfunction "2_2") (pintype "passive"))
      (node (ref "C95") (pin "2") (pinfunction "2_2") (pintype "passive"))
      (node (ref "C96") (pin "2") (pinfunction "2_2") (pintype "passive"))
      (node (ref "C97") (pin "2") (pinfunction "2_2") (pintype "passive"))
      (node (ref "C98") (pin "2") (pinfunction "2_2") (pintype "passive"))
      (node (ref "C99") (pin "2") (pinfunction "2_2") (pintype "passive"))
      (node (ref "U2") (pin "A1") (pinfunction "Vdd1_A1") (pintype "power_in"))
      (node (ref "U2") (pin "A9") (pinfunction "VddQ1_A9") (pintype "power_in"))
      (node (ref "U2") (pin "C1") (pinfunction "VddQ2_C1") (pintype "power_in"))
      (node (ref "U2") (pin "C3") (pinfunction "VddQ3_C3") (pintype "power_in"))
      (node (ref "U2") (pin "C7") (pinfunction "VddQ4_C7") (pintype "power_in"))
      (node (ref "U2") (pin "C9") (pinfunction "VddQ5_C9") (pintype "power_in"))
      (node (ref "U2") (pin "E1") (pinfunction "Vdd2_E1") (pintype "power_in"))
      (node (ref "U2") (pin "E9") (pinfunction "VddQ6_E9") (pintype "power_in"))
      (node (ref "U2") (pin "G1") (pinfunction "VddQ7_G1") (pintype "power_in"))
      (node (ref "U2") (pin "G3") (pinfunction "VddQ8_G3") (pintype "power_in"))
      (node (ref "U2") (pin "G7") (pinfunction "VddQ9_G7") (pintype "power_in"))
      (node (ref "U2") (pin "G9") (pinfunction "VddQ10_G9") (pintype "power_in"))
      (node (ref "U2") (pin "J1") (pinfunction "V_DLL_J1") (pintype "power_in"))
      (node (ref "U2") (pin "J9") (pinfunction "Vdd4_J9") (pintype "power_in"))
      (node (ref "U2") (pin "M9") (pinfunction "Vdd3_M9") (pintype "power_in"))
      (node (ref "U2") (pin "R1") (pinfunction "Vdd5_R1") (pintype "power_in"))
    )
    (net (code "57") (name "VCC3V3") (class "Default")
      (node (ref "C54") (pin "2") (pinfunction "2_2") (pintype "passive"))
      (node (ref "R31") (pin "1") (pinfunction "1_1") (pintype "passive"))
      (node (ref "R33") (pin "1") (pinfunction "1_1") (pintype "passive"))
      (node (ref "U20") (pin "8") (pinfunction "VCC_8") (pintype "power_in"))
    )
    (net (code "58") (name "unconnected-(R69-Pad6)") (class "Default")
      (node (ref "R69") (pin "6") (pinfunction "6_6") (pintype "passive"))
    )
    (net (code "59") (name "unconnected-(R69-Pad7)") (class "Default")
      (node (ref "R69") (pin "7") (pinfunction "7_7") (pintype "passive"))
    )
    (net (code "60") (name "unconnected-(R69-Pad8)") (class "Default")
      (node (ref "R69") (pin "8") (pinfunction "8_8") (pintype "passive"))
    )
    (net (code "61") (name "unconnected-(U1D-IO_L2N_3-PadW1)") (class "Default")
      (node (ref "U1") (pin "W1") (pinfunction "IO_L2N_3_W1") (pintype "bidirectional"))
    )
    (net (code "62") (name "unconnected-(U1D-IO_L7N_3-PadP7)") (class "Default")
      (node (ref "U1") (pin "P7") (pinfunction "IO_L7N_3_P7") (pintype "bidirectional"))
    )
    (net (code "63") (name "unconnected-(U1D-IO_L7P_3-PadP8)") (class "Default")
      (node (ref "U1") (pin "P8") (pinfunction "IO_L7P_3_P8") (pintype "bidirectional"))
    )
    (net (code "64") (name "unconnected-(U1D-IO_L8N_3-PadP5)") (class "Default")
      (node (ref "U1") (pin "P5") (pinfunction "IO_L8N_3_P5") (pintype "bidirectional"))
    )
    (net (code "65") (name "unconnected-(U1D-IO_L8P_3-PadP6)") (class "Default")
      (node (ref "U1") (pin "P6") (pinfunction "IO_L8P_3_P6") (pintype "bidirectional"))
    )
    (net (code "66") (name "unconnected-(U1D-IO_L9N_3-PadT3)") (class "Default")
      (node (ref "U1") (pin "T3") (pinfunction "IO_L9N_3_T3") (pintype "bidirectional"))
    )
    (net (code "67") (name "unconnected-(U1D-IO_L9P_3-PadT4)") (class "Default")
      (node (ref "U1") (pin "T4") (pinfunction "IO_L9P_3_T4") (pintype "bidirectional"))
    )
    (net (code "68") (name "unconnected-(U1D-IO_L10N_3-PadV3)") (class "Default")
      (node (ref "U1") (pin "V3") (pinfunction "IO_L10N_3_V3") (pintype "bidirectional"))
    )
    (net (code "69") (name "unconnected-(U1D-IO_L10P_3-PadU4)") (class "Default")
      (node (ref "U1") (pin "U4") (pinfunction "IO_L10P_3_U4") (pintype "bidirectional"))
    )
    (net (code "70") (name "unconnected-(U1D-IO_L11N_3-PadN7)") (class "Default")
      (node (ref "U1") (pin "N7") (pinfunction "IO_L11N_3_N7") (pintype "bidirectional"))
    )
    (net (code "71") (name "unconnected-(U1D-IO_L11P_3-PadN6)") (class "Default")
      (node (ref "U1") (pin "N6") (pinfunction "IO_L11P_3_N6") (pintype "bidirectional"))
    )
    (net (code "72") (name "unconnected-(U1D-IO_L23N_3-PadM8)") (class "Default")
      (node (ref "U1") (pin "M8") (pinfunction "IO_L23N_3_M8") (pintype "bidirectional"))
    )
    (net (code "73") (name "unconnected-(U1D-IO_L23P_3-PadM7)") (class "Default")
      (node (ref "U1") (pin "M7") (pinfunction "IO_L23P_3_M7") (pintype "bidirectional"))
    )
    (net (code "74") (name "unconnected-(U1D-IO_L24N_3-PadP4)") (class "Default")
      (node (ref "U1") (pin "P4") (pinfunction "IO_L24N_3_P4") (pintype "bidirectional"))
    )
    (net (code "75") (name "unconnected-(U1D-IO_L24P_3-PadR4)") (class "Default")
      (node (ref "U1") (pin "R4") (pinfunction "IO_L24P_3_R4") (pintype "bidirectional"))
    )
    (net (code "76") (name "unconnected-(U1D-IO_L25N_3-PadL6)") (class "Default")
      (node (ref "U1") (pin "L6") (pinfunction "IO_L25N_3_L6") (pintype "bidirectional"))
    )
    (net (code "77") (name "unconnected-(U1D-IO_L25P_3-PadM6)") (class "Default")
      (node (ref "U1") (pin "M6") (pinfunction "IO_L25P_3_M6") (pintype "bidirectional"))
    )
    (net (code "78") (name "unconnected-(U1D-IO_L26N_3-PadN4)") (class "Default")
      (node (ref "U1") (pin "N4") (pinfunction "IO_L26N_3_N4") (pintype "bidirectional"))
    )
    (net (code "79") (name "unconnected-(U1D-IO_L26P_3-PadP3)") (class "Default")
      (node (ref "U1") (pin "P3") (pinfunction "IO_L26P_3_P3") (pintype "bidirectional"))
    )
    (net (code "80") (name "unconnected-(U1D-IO_L31P_3-PadM5)") (class "Default")
      (node (ref "U1") (pin "M5") (pinfunction "IO_L31P_3_M5") (pintype "bidirectional"))
    )
    (net (code "81") (name "unconnected-(U1D-IO_L54P_M3RESET_3-PadC3)") (class "Default")
      (node (ref "U1") (pin "C3") (pinfunction "IO_L54P_M3RESET_3_C3") (pintype "bidirectional"))
    )
    (net (code "82") (name "unconnected-(U1D-IO_L57P_3-PadK7)") (class "Default")
      (node (ref "U1") (pin "K7") (pinfunction "IO_L57P_3_K7") (pintype "bidirectional"))
    )
    (net (code "83") (name "unconnected-(U1D-IO_L58N_3-PadE4)") (class "Default")
      (node (ref "U1") (pin "E4") (pinfunction "IO_L58N_3_E4") (pintype "bidirectional"))
    )
    (net (code "84") (name "unconnected-(U1D-IO_L58P_3-PadD5)") (class "Default")
      (node (ref "U1") (pin "D5") (pinfunction "IO_L58P_3_D5") (pintype "bidirectional"))
    )
    (net (code "85") (name "unconnected-(U1D-IO_L59N_3-PadH8)") (class "Default")
      (node (ref "U1") (pin "H8") (pinfunction "IO_L59N_3_H8") (pintype "bidirectional"))
    )
    (net (code "86") (name "unconnected-(U1D-IO_L59P_3-PadJ7)") (class "Default")
      (node (ref "U1") (pin "J7") (pinfunction "IO_L59P_3_J7") (pintype "bidirectional"))
    )
    (net (code "87") (name "unconnected-(U1D-IO_L80N_3-PadF7)") (class "Default")
      (node (ref "U1") (pin "F7") (pinfunction "IO_L80N_3_F7") (pintype "bidirectional"))
    )
    (net (code "88") (name "unconnected-(U1D-IO_L80P_3-PadG7)") (class "Default")
      (node (ref "U1") (pin "G7") (pinfunction "IO_L80P_3_G7") (pintype "bidirectional"))
    )
    (net (code "89") (name "unconnected-(U1D-IO_L81N_3-PadC4)") (class "Default")
      (node (ref "U1") (pin "C4") (pinfunction "IO_L81N_3_C4") (pintype "bidirectional"))
    )
    (net (code "90") (name "unconnected-(U1D-IO_L81P_3-PadD3)") (class "Default")
      (node (ref "U1") (pin "D3") (pinfunction "IO_L81P_3_D3") (pintype "bidirectional"))
    )
    (net (code "91") (name "unconnected-(U1D-IO_L82N_3-PadE6)") (class "Default")
      (node (ref "U1") (pin "E6") (pinfunction "IO_L82N_3_E6") (pintype "bidirectional"))
    )
    (net (code "92") (name "unconnected-(U1D-IO_L82P_3-PadE5)") (class "Default")
      (node (ref "U1") (pin "E5") (pinfunction "IO_L82P_3_E5") (pintype "bidirectional"))
    )
    (net (code "93") (name "unconnected-(U1D-IO_L83P_3-PadA2)") (class "Default")
      (node (ref "U1") (pin "A2") (pinfunction "IO_L83P_3_A2") (pintype "bidirectional"))
    )
    (net (code "94") (name "unconnected-(U2A-NC1-PadA2)") (class "Default")
      (node (ref "U2") (pin "A2") (pinfunction "NC1_A2") (pintype "passive"))
    )
    (net (code "95") (name "unconnected-(U2A-NC2-PadE2)") (class "Default")
      (node (ref "U2") (pin "E2") (pinfunction "NC2_E2") (pintype "passive"))
    )
    (net (code "96") (name "unconnected-(U2A-NC_A15-PadR7)") (class "Default")
      (node (ref "U2") (pin "R7") (pinfunction "NC_A15_R7") (pintype "input"))
    )
  )
)
